# ziggy.net
KiCad netlist of a schematic drawn in EAGLE
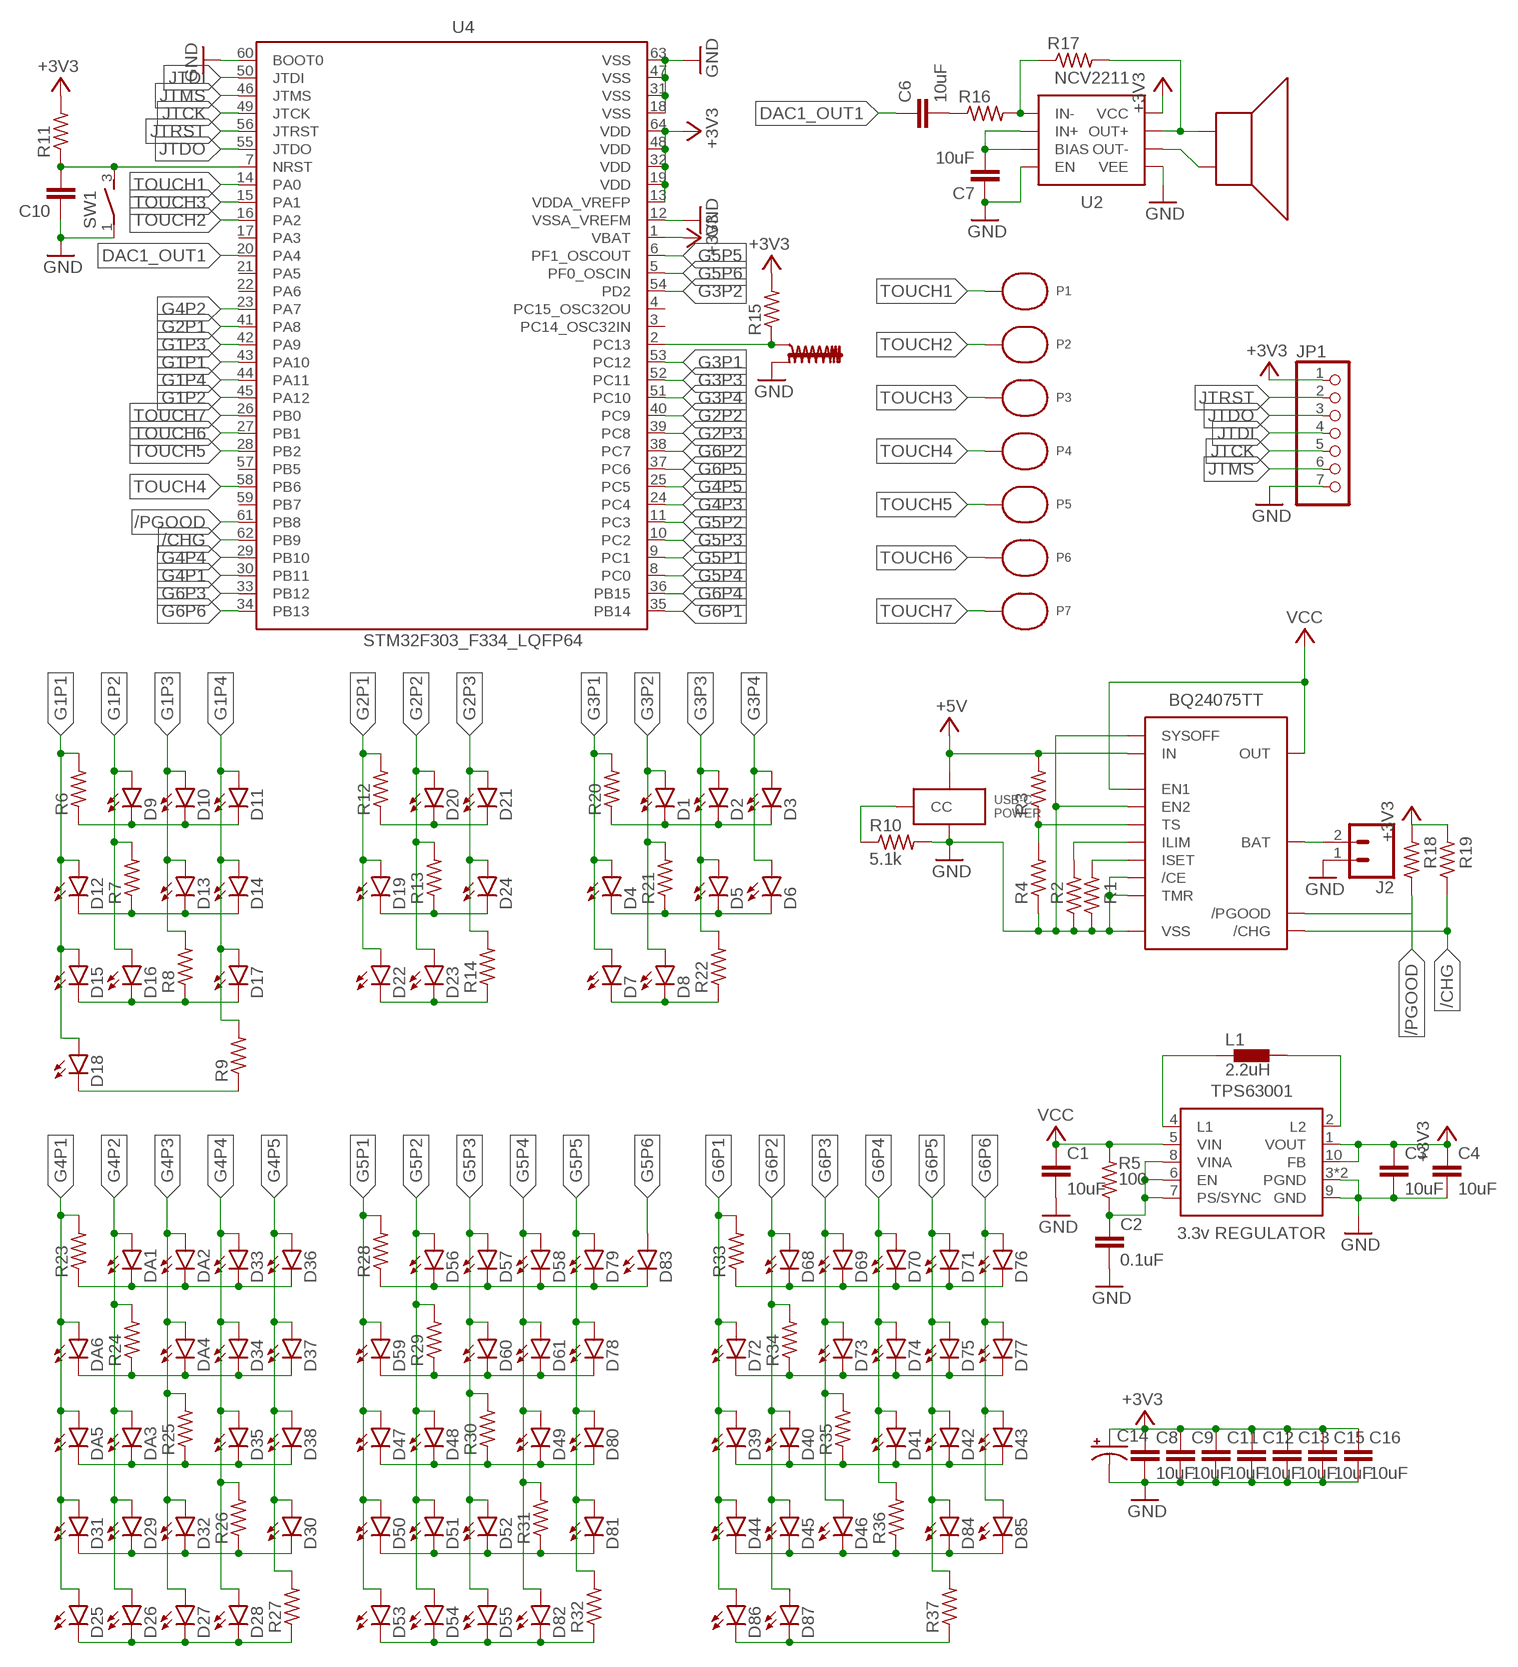
[diagram p0: schematic, sheet 1]

(export (version "E")
  (design (tool "Eeschema 10.0.6"))
  (components
    (comp (ref "C1")
      (value "10uF")
      (footprint "eagle-import:C0805")
      (libsource (lib "eagle-import") (part "C-EUC0805"))
    )
    (comp (ref "C2")
      (value "0.1uF")
      (footprint "eagle-import:C0805")
      (libsource (lib "eagle-import") (part "C-EUC0805"))
    )
    (comp (ref "C3")
      (value "10uF")
      (footprint "eagle-import:C0805")
      (libsource (lib "eagle-import") (part "C-EUC0805"))
    )
    (comp (ref "C4")
      (value "10uF")
      (footprint "eagle-import:C0805")
      (libsource (lib "eagle-import") (part "C-EUC0805"))
    )
    (comp (ref "C6")
      (value "10uF")
      (footprint "eagle-import:C0805")
      (libsource (lib "eagle-import") (part "C-EUC0805"))
    )
    (comp (ref "C7")
      (value "10uF")
      (footprint "eagle-import:C0805")
      (libsource (lib "eagle-import") (part "C-EUC0805"))
    )
    (comp (ref "C8")
      (value "10uF")
      (footprint "eagle-import:C0805")
      (libsource (lib "eagle-import") (part "C-EUC0805"))
    )
    (comp (ref "C9")
      (value "10uF")
      (footprint "eagle-import:C0805")
      (libsource (lib "eagle-import") (part "C-EUC0805"))
    )
    (comp (ref "C10")
      (value "C-EUC0805")
      (footprint "eagle-import:C0805")
      (libsource (lib "eagle-import") (part "C-EUC0805"))
    )
    (comp (ref "C11")
      (value "10uF")
      (footprint "eagle-import:C0805")
      (libsource (lib "eagle-import") (part "C-EUC0805"))
    )
    (comp (ref "C12")
      (value "10uF")
      (footprint "eagle-import:C0805")
      (libsource (lib "eagle-import") (part "C-EUC0805"))
    )
    (comp (ref "C13")
      (value "10uF")
      (footprint "eagle-import:C0805")
      (libsource (lib "eagle-import") (part "C-EUC0805"))
    )
    (comp (ref "C14")
      (value "CPOL-US153CLV-0810")
      (footprint "eagle-import:153CLV-0810")
      (libsource (lib "eagle-import") (part "CPOL-US153CLV-0810"))
    )
    (comp (ref "C15")
      (value "10uF")
      (footprint "eagle-import:C0805")
      (libsource (lib "eagle-import") (part "C-EUC0805"))
    )
    (comp (ref "C16")
      (value "10uF")
      (footprint "eagle-import:C0805")
      (libsource (lib "eagle-import") (part "C-EUC0805"))
    )
    (comp (ref "D1")
      (value "LED-0805")
      (footprint "eagle-import:CHIPLED_0805")
      (libsource (lib "eagle-import") (part "LED-0805"))
    )
    (comp (ref "D2")
      (value "LED-0805")
      (footprint "eagle-import:CHIPLED_0805")
      (libsource (lib "eagle-import") (part "LED-0805"))
    )
    (comp (ref "D3")
      (value "LED-0805")
      (footprint "eagle-import:CHIPLED_0805")
      (libsource (lib "eagle-import") (part "LED-0805"))
    )
    (comp (ref "D4")
      (value "LED-0805")
      (footprint "eagle-import:CHIPLED_0805")
      (libsource (lib "eagle-import") (part "LED-0805"))
    )
    (comp (ref "D5")
      (value "LED-0805")
      (footprint "eagle-import:CHIPLED_0805")
      (libsource (lib "eagle-import") (part "LED-0805"))
    )
    (comp (ref "D6")
      (value "LED-0805")
      (footprint "eagle-import:CHIPLED_0805")
      (libsource (lib "eagle-import") (part "LED-0805"))
    )
    (comp (ref "D7")
      (value "LED-0805")
      (footprint "eagle-import:CHIPLED_0805")
      (libsource (lib "eagle-import") (part "LED-0805"))
    )
    (comp (ref "D8")
      (value "LED-0805")
      (footprint "eagle-import:CHIPLED_0805")
      (libsource (lib "eagle-import") (part "LED-0805"))
    )
    (comp (ref "D9")
      (value "LED-0805")
      (footprint "eagle-import:CHIPLED_0805")
      (libsource (lib "eagle-import") (part "LED-0805"))
    )
    (comp (ref "D10")
      (value "LED-0805")
      (footprint "eagle-import:CHIPLED_0805")
      (libsource (lib "eagle-import") (part "LED-0805"))
    )
    (comp (ref "D11")
      (value "LED-0805")
      (footprint "eagle-import:CHIPLED_0805")
      (libsource (lib "eagle-import") (part "LED-0805"))
    )
    (comp (ref "D12")
      (value "LED-0805")
      (footprint "eagle-import:CHIPLED_0805")
      (libsource (lib "eagle-import") (part "LED-0805"))
    )
    (comp (ref "D13")
      (value "LED-0805")
      (footprint "eagle-import:CHIPLED_0805")
      (libsource (lib "eagle-import") (part "LED-0805"))
    )
    (comp (ref "D14")
      (value "LED-0805")
      (footprint "eagle-import:CHIPLED_0805")
      (libsource (lib "eagle-import") (part "LED-0805"))
    )
    (comp (ref "D15")
      (value "LED-0805")
      (footprint "eagle-import:CHIPLED_0805")
      (libsource (lib "eagle-import") (part "LED-0805"))
    )
    (comp (ref "D16")
      (value "LED-0805")
      (footprint "eagle-import:CHIPLED_0805")
      (libsource (lib "eagle-import") (part "LED-0805"))
    )
    (comp (ref "D17")
      (value "LED-0805")
      (footprint "eagle-import:CHIPLED_0805")
      (libsource (lib "eagle-import") (part "LED-0805"))
    )
    (comp (ref "D18")
      (value "LED-0805")
      (footprint "eagle-import:CHIPLED_0805")
      (libsource (lib "eagle-import") (part "LED-0805"))
    )
    (comp (ref "D19")
      (value "LED-0805")
      (footprint "eagle-import:CHIPLED_0805")
      (libsource (lib "eagle-import") (part "LED-0805"))
    )
    (comp (ref "D20")
      (value "LED-0805")
      (footprint "eagle-import:CHIPLED_0805")
      (libsource (lib "eagle-import") (part "LED-0805"))
    )
    (comp (ref "D21")
      (value "LED-0805")
      (footprint "eagle-import:CHIPLED_0805")
      (libsource (lib "eagle-import") (part "LED-0805"))
    )
    (comp (ref "D22")
      (value "LED-0805")
      (footprint "eagle-import:CHIPLED_0805")
      (libsource (lib "eagle-import") (part "LED-0805"))
    )
    (comp (ref "D23")
      (value "LED-0805")
      (footprint "eagle-import:CHIPLED_0805")
      (libsource (lib "eagle-import") (part "LED-0805"))
    )
    (comp (ref "D24")
      (value "LED-0805")
      (footprint "eagle-import:CHIPLED_0805")
      (libsource (lib "eagle-import") (part "LED-0805"))
    )
    (comp (ref "D25")
      (value "LED-0805")
      (footprint "eagle-import:CHIPLED_0805")
      (libsource (lib "eagle-import") (part "LED-0805"))
    )
    (comp (ref "D26")
      (value "LED-0805")
      (footprint "eagle-import:CHIPLED_0805")
      (libsource (lib "eagle-import") (part "LED-0805"))
    )
    (comp (ref "D27")
      (value "LED-0805")
      (footprint "eagle-import:CHIPLED_0805")
      (libsource (lib "eagle-import") (part "LED-0805"))
    )
    (comp (ref "D28")
      (value "LED-0805")
      (footprint "eagle-import:CHIPLED_0805")
      (libsource (lib "eagle-import") (part "LED-0805"))
    )
    (comp (ref "D29")
      (value "LED-0805")
      (footprint "eagle-import:CHIPLED_0805")
      (libsource (lib "eagle-import") (part "LED-0805"))
    )
    (comp (ref "D30")
      (value "LED-0805")
      (footprint "eagle-import:CHIPLED_0805")
      (libsource (lib "eagle-import") (part "LED-0805"))
    )
    (comp (ref "D31")
      (value "LED-0805")
      (footprint "eagle-import:CHIPLED_0805")
      (libsource (lib "eagle-import") (part "LED-0805"))
    )
    (comp (ref "D32")
      (value "LED-0805")
      (footprint "eagle-import:CHIPLED_0805")
      (libsource (lib "eagle-import") (part "LED-0805"))
    )
    (comp (ref "D33")
      (value "LED-0805")
      (footprint "eagle-import:CHIPLED_0805")
      (libsource (lib "eagle-import") (part "LED-0805"))
    )
    (comp (ref "D34")
      (value "LED-0805")
      (footprint "eagle-import:CHIPLED_0805")
      (libsource (lib "eagle-import") (part "LED-0805"))
    )
    (comp (ref "D35")
      (value "LED-0805")
      (footprint "eagle-import:CHIPLED_0805")
      (libsource (lib "eagle-import") (part "LED-0805"))
    )
    (comp (ref "D36")
      (value "LED-0805")
      (footprint "eagle-import:CHIPLED_0805")
      (libsource (lib "eagle-import") (part "LED-0805"))
    )
    (comp (ref "D37")
      (value "LED-0805")
      (footprint "eagle-import:CHIPLED_0805")
      (libsource (lib "eagle-import") (part "LED-0805"))
    )
    (comp (ref "D38")
      (value "LED-0805")
      (footprint "eagle-import:CHIPLED_0805")
      (libsource (lib "eagle-import") (part "LED-0805"))
    )
    (comp (ref "D39")
      (value "LED-0805")
      (footprint "eagle-import:CHIPLED_0805")
      (libsource (lib "eagle-import") (part "LED-0805"))
    )
    (comp (ref "D40")
      (value "LED-0805")
      (footprint "eagle-import:CHIPLED_0805")
      (libsource (lib "eagle-import") (part "LED-0805"))
    )
    (comp (ref "D41")
      (value "LED-0805")
      (footprint "eagle-import:CHIPLED_0805")
      (libsource (lib "eagle-import") (part "LED-0805"))
    )
    (comp (ref "D42")
      (value "LED-0805")
      (footprint "eagle-import:CHIPLED_0805")
      (libsource (lib "eagle-import") (part "LED-0805"))
    )
    (comp (ref "D43")
      (value "LED-0805")
      (footprint "eagle-import:CHIPLED_0805")
      (libsource (lib "eagle-import") (part "LED-0805"))
    )
    (comp (ref "D44")
      (value "LED-0805")
      (footprint "eagle-import:CHIPLED_0805")
      (libsource (lib "eagle-import") (part "LED-0805"))
    )
    (comp (ref "D45")
      (value "LED-0805")
      (footprint "eagle-import:CHIPLED_0805")
      (libsource (lib "eagle-import") (part "LED-0805"))
    )
    (comp (ref "D46")
      (value "LED-0805")
      (footprint "eagle-import:CHIPLED_0805")
      (libsource (lib "eagle-import") (part "LED-0805"))
    )
    (comp (ref "D47")
      (value "LED-0805")
      (footprint "eagle-import:CHIPLED_0805")
      (libsource (lib "eagle-import") (part "LED-0805"))
    )
    (comp (ref "D48")
      (value "LED-0805")
      (footprint "eagle-import:CHIPLED_0805")
      (libsource (lib "eagle-import") (part "LED-0805"))
    )
    (comp (ref "D49")
      (value "LED-0805")
      (footprint "eagle-import:CHIPLED_0805")
      (libsource (lib "eagle-import") (part "LED-0805"))
    )
    (comp (ref "D50")
      (value "LED-0805")
      (footprint "eagle-import:CHIPLED_0805")
      (libsource (lib "eagle-import") (part "LED-0805"))
    )
    (comp (ref "D51")
      (value "LED-0805")
      (footprint "eagle-import:CHIPLED_0805")
      (libsource (lib "eagle-import") (part "LED-0805"))
    )
    (comp (ref "D52")
      (value "LED-0805")
      (footprint "eagle-import:CHIPLED_0805")
      (libsource (lib "eagle-import") (part "LED-0805"))
    )
    (comp (ref "D53")
      (value "LED-0805")
      (footprint "eagle-import:CHIPLED_0805")
      (libsource (lib "eagle-import") (part "LED-0805"))
    )
    (comp (ref "D54")
      (value "LED-0805")
      (footprint "eagle-import:CHIPLED_0805")
      (libsource (lib "eagle-import") (part "LED-0805"))
    )
    (comp (ref "D55")
      (value "LED-0805")
      (footprint "eagle-import:CHIPLED_0805")
      (libsource (lib "eagle-import") (part "LED-0805"))
    )
    (comp (ref "D56")
      (value "LED-0805")
      (footprint "eagle-import:CHIPLED_0805")
      (libsource (lib "eagle-import") (part "LED-0805"))
    )
    (comp (ref "D57")
      (value "LED-0805")
      (footprint "eagle-import:CHIPLED_0805")
      (libsource (lib "eagle-import") (part "LED-0805"))
    )
    (comp (ref "D58")
      (value "LED-0805")
      (footprint "eagle-import:CHIPLED_0805")
      (libsource (lib "eagle-import") (part "LED-0805"))
    )
    (comp (ref "D59")
      (value "LED-0805")
      (footprint "eagle-import:CHIPLED_0805")
      (libsource (lib "eagle-import") (part "LED-0805"))
    )
    (comp (ref "D60")
      (value "LED-0805")
      (footprint "eagle-import:CHIPLED_0805")
      (libsource (lib "eagle-import") (part "LED-0805"))
    )
    (comp (ref "D61")
      (value "LED-0805")
      (footprint "eagle-import:CHIPLED_0805")
      (libsource (lib "eagle-import") (part "LED-0805"))
    )
    (comp (ref "D68")
      (value "LED-0805")
      (footprint "eagle-import:CHIPLED_0805")
      (libsource (lib "eagle-import") (part "LED-0805"))
    )
    (comp (ref "D69")
      (value "LED-0805")
      (footprint "eagle-import:CHIPLED_0805")
      (libsource (lib "eagle-import") (part "LED-0805"))
    )
    (comp (ref "D70")
      (value "LED-0805")
      (footprint "eagle-import:CHIPLED_0805")
      (libsource (lib "eagle-import") (part "LED-0805"))
    )
    (comp (ref "D71")
      (value "LED-0805")
      (footprint "eagle-import:CHIPLED_0805")
      (libsource (lib "eagle-import") (part "LED-0805"))
    )
    (comp (ref "D72")
      (value "LED-0805")
      (footprint "eagle-import:CHIPLED_0805")
      (libsource (lib "eagle-import") (part "LED-0805"))
    )
    (comp (ref "D73")
      (value "LED-0805")
      (footprint "eagle-import:CHIPLED_0805")
      (libsource (lib "eagle-import") (part "LED-0805"))
    )
    (comp (ref "D74")
      (value "LED-0805")
      (footprint "eagle-import:CHIPLED_0805")
      (libsource (lib "eagle-import") (part "LED-0805"))
    )
    (comp (ref "D75")
      (value "LED-0805")
      (footprint "eagle-import:CHIPLED_0805")
      (libsource (lib "eagle-import") (part "LED-0805"))
    )
    (comp (ref "D76")
      (value "LED-0805")
      (footprint "eagle-import:CHIPLED_0805")
      (libsource (lib "eagle-import") (part "LED-0805"))
    )
    (comp (ref "D77")
      (value "LED-0805")
      (footprint "eagle-import:CHIPLED_0805")
      (libsource (lib "eagle-import") (part "LED-0805"))
    )
    (comp (ref "D78")
      (value "LED-0805")
      (footprint "eagle-import:CHIPLED_0805")
      (libsource (lib "eagle-import") (part "LED-0805"))
    )
    (comp (ref "D79")
      (value "LED-0805")
      (footprint "eagle-import:CHIPLED_0805")
      (libsource (lib "eagle-import") (part "LED-0805"))
    )
    (comp (ref "D80")
      (value "LED-0805")
      (footprint "eagle-import:CHIPLED_0805")
      (libsource (lib "eagle-import") (part "LED-0805"))
    )
    (comp (ref "D81")
      (value "LED-0805")
      (footprint "eagle-import:CHIPLED_0805")
      (libsource (lib "eagle-import") (part "LED-0805"))
    )
    (comp (ref "D82")
      (value "LED-0805")
      (footprint "eagle-import:CHIPLED_0805")
      (libsource (lib "eagle-import") (part "LED-0805"))
    )
    (comp (ref "D83")
      (value "LED-0805")
      (footprint "eagle-import:CHIPLED_0805")
      (libsource (lib "eagle-import") (part "LED-0805"))
    )
    (comp (ref "D84")
      (value "LED-0805")
      (footprint "eagle-import:CHIPLED_0805")
      (libsource (lib "eagle-import") (part "LED-0805"))
    )
    (comp (ref "D85")
      (value "LED-0805")
      (footprint "eagle-import:CHIPLED_0805")
      (libsource (lib "eagle-import") (part "LED-0805"))
    )
    (comp (ref "D86")
      (value "LED-0805")
      (footprint "eagle-import:CHIPLED_0805")
      (libsource (lib "eagle-import") (part "LED-0805"))
    )
    (comp (ref "D87")
      (value "LED-0805")
      (footprint "eagle-import:CHIPLED_0805")
      (libsource (lib "eagle-import") (part "LED-0805"))
    )
    (comp (ref "DA1")
      (value "LED-0805")
      (footprint "eagle-import:CHIPLED_0805")
      (libsource (lib "eagle-import") (part "LED-0805"))
    )
    (comp (ref "DA2")
      (value "LED-0805")
      (footprint "eagle-import:CHIPLED_0805")
      (libsource (lib "eagle-import") (part "LED-0805"))
    )
    (comp (ref "DA3")
      (value "LED-0805")
      (footprint "eagle-import:CHIPLED_0805")
      (libsource (lib "eagle-import") (part "LED-0805"))
    )
    (comp (ref "DA4")
      (value "LED-0805")
      (footprint "eagle-import:CHIPLED_0805")
      (libsource (lib "eagle-import") (part "LED-0805"))
    )
    (comp (ref "DA5")
      (value "LED-0805")
      (footprint "eagle-import:CHIPLED_0805")
      (libsource (lib "eagle-import") (part "LED-0805"))
    )
    (comp (ref "DA6")
      (value "LED-0805")
      (footprint "eagle-import:CHIPLED_0805")
      (libsource (lib "eagle-import") (part "LED-0805"))
    )
    (comp (ref "J1")
      (value "USB-C-POWER")
      (footprint "eagle-import:USB-C")
      (libsource (lib "eagle-import") (part "USB-C-POWER"))
    )
    (comp (ref "J2")
      (value "CONN_02-JST-2MM-SMT")
      (footprint "eagle-import:JST-2-SMD")
      (libsource (lib "eagle-import") (part "CONN_02-JST-2MM-SMT"))
    )
    (comp (ref "JP1")
      (value "PINHD-1X7/90")
      (footprint "eagle-import:1X07_90")
      (libsource (lib "eagle-import") (part "PINHD-1X7/90"))
    )
    (comp (ref "L1")
      (value "2.2uH")
      (footprint "eagle-import:LPS3015")
      (libsource (lib "eagle-import") (part "LPS3015"))
    )
    (comp (ref "P1")
      (value "CAPTOUCH")
      (footprint "eagle-import:CAPTOUCH")
      (libsource (lib "eagle-import") (part "CAPTOUCH"))
    )
    (comp (ref "P2")
      (value "CAPTOUCH")
      (footprint "eagle-import:CAPTOUCH")
      (libsource (lib "eagle-import") (part "CAPTOUCH"))
    )
    (comp (ref "P3")
      (value "CAPTOUCH")
      (footprint "eagle-import:CAPTOUCH")
      (libsource (lib "eagle-import") (part "CAPTOUCH"))
    )
    (comp (ref "P4")
      (value "CAPTOUCH")
      (footprint "eagle-import:CAPTOUCH")
      (libsource (lib "eagle-import") (part "CAPTOUCH"))
    )
    (comp (ref "P5")
      (value "CAPTOUCH")
      (footprint "eagle-import:CAPTOUCH")
      (libsource (lib "eagle-import") (part "CAPTOUCH"))
    )
    (comp (ref "P6")
      (value "CAPTOUCH")
      (footprint "eagle-import:CAPTOUCH")
      (libsource (lib "eagle-import") (part "CAPTOUCH"))
    )
    (comp (ref "P7")
      (value "CAPTOUCH")
      (footprint "eagle-import:CAPTOUCH")
      (libsource (lib "eagle-import") (part "CAPTOUCH"))
    )
    (comp (ref "R1")
      (value "R-US_R0805")
      (footprint "eagle-import:R0805")
      (libsource (lib "eagle-import") (part "R-US_R0805"))
    )
    (comp (ref "R2")
      (value "R-US_R0805")
      (footprint "eagle-import:R0805")
      (libsource (lib "eagle-import") (part "R-US_R0805"))
    )
    (comp (ref "R3")
      (value "R-US_R0805")
      (footprint "eagle-import:R0805")
      (libsource (lib "eagle-import") (part "R-US_R0805"))
    )
    (comp (ref "R4")
      (value "R-US_R0805")
      (footprint "eagle-import:R0805")
      (libsource (lib "eagle-import") (part "R-US_R0805"))
    )
    (comp (ref "R5")
      (value "100")
      (footprint "eagle-import:R0805")
      (libsource (lib "eagle-import") (part "R-US_R0805"))
    )
    (comp (ref "R6")
      (value "R-US_R0805")
      (footprint "eagle-import:R0805")
      (libsource (lib "eagle-import") (part "R-US_R0805"))
    )
    (comp (ref "R7")
      (value "R-US_R0805")
      (footprint "eagle-import:R0805")
      (libsource (lib "eagle-import") (part "R-US_R0805"))
    )
    (comp (ref "R8")
      (value "R-US_R0805")
      (footprint "eagle-import:R0805")
      (libsource (lib "eagle-import") (part "R-US_R0805"))
    )
    (comp (ref "R9")
      (value "R-US_R0805")
      (footprint "eagle-import:R0805")
      (libsource (lib "eagle-import") (part "R-US_R0805"))
    )
    (comp (ref "R10")
      (value "5.1k")
      (footprint "eagle-import:R0805")
      (libsource (lib "eagle-import") (part "R-US_R0805"))
    )
    (comp (ref "R11")
      (value "R-US_R0805")
      (footprint "eagle-import:R0805")
      (libsource (lib "eagle-import") (part "R-US_R0805"))
    )
    (comp (ref "R12")
      (value "R-US_R0805")
      (footprint "eagle-import:R0805")
      (libsource (lib "eagle-import") (part "R-US_R0805"))
    )
    (comp (ref "R13")
      (value "R-US_R0805")
      (footprint "eagle-import:R0805")
      (libsource (lib "eagle-import") (part "R-US_R0805"))
    )
    (comp (ref "R14")
      (value "R-US_R0805")
      (footprint "eagle-import:R0805")
      (libsource (lib "eagle-import") (part "R-US_R0805"))
    )
    (comp (ref "R15")
      (value "R-US_R0805")
      (footprint "eagle-import:R0805")
      (libsource (lib "eagle-import") (part "R-US_R0805"))
    )
    (comp (ref "R16")
      (value "R-US_R0805")
      (footprint "eagle-import:R0805")
      (libsource (lib "eagle-import") (part "R-US_R0805"))
    )
    (comp (ref "R17")
      (value "R-US_R0805")
      (footprint "eagle-import:R0805")
      (libsource (lib "eagle-import") (part "R-US_R0805"))
    )
    (comp (ref "R18")
      (value "R-US_R0805")
      (footprint "eagle-import:R0805")
      (libsource (lib "eagle-import") (part "R-US_R0805"))
    )
    (comp (ref "R19")
      (value "R-US_R0805")
      (footprint "eagle-import:R0805")
      (libsource (lib "eagle-import") (part "R-US_R0805"))
    )
    (comp (ref "R20")
      (value "R-US_R0805")
      (footprint "eagle-import:R0805")
      (libsource (lib "eagle-import") (part "R-US_R0805"))
    )
    (comp (ref "R21")
      (value "R-US_R0805")
      (footprint "eagle-import:R0805")
      (libsource (lib "eagle-import") (part "R-US_R0805"))
    )
    (comp (ref "R22")
      (value "R-US_R0805")
      (footprint "eagle-import:R0805")
      (libsource (lib "eagle-import") (part "R-US_R0805"))
    )
    (comp (ref "R23")
      (value "R-US_R0805")
      (footprint "eagle-import:R0805")
      (libsource (lib "eagle-import") (part "R-US_R0805"))
    )
    (comp (ref "R24")
      (value "R-US_R0805")
      (footprint "eagle-import:R0805")
      (libsource (lib "eagle-import") (part "R-US_R0805"))
    )
    (comp (ref "R25")
      (value "R-US_R0805")
      (footprint "eagle-import:R0805")
      (libsource (lib "eagle-import") (part "R-US_R0805"))
    )
    (comp (ref "R26")
      (value "R-US_R0805")
      (footprint "eagle-import:R0805")
      (libsource (lib "eagle-import") (part "R-US_R0805"))
    )
    (comp (ref "R27")
      (value "R-US_R0805")
      (footprint "eagle-import:R0805")
      (libsource (lib "eagle-import") (part "R-US_R0805"))
    )
    (comp (ref "R28")
      (value "R-US_R0805")
      (footprint "eagle-import:R0805")
      (libsource (lib "eagle-import") (part "R-US_R0805"))
    )
    (comp (ref "R29")
      (value "R-US_R0805")
      (footprint "eagle-import:R0805")
      (libsource (lib "eagle-import") (part "R-US_R0805"))
    )
    (comp (ref "R30")
      (value "R-US_R0805")
      (footprint "eagle-import:R0805")
      (libsource (lib "eagle-import") (part "R-US_R0805"))
    )
    (comp (ref "R31")
      (value "R-US_R0805")
      (footprint "eagle-import:R0805")
      (libsource (lib "eagle-import") (part "R-US_R0805"))
    )
    (comp (ref "R32")
      (value "R-US_R0805")
      (footprint "eagle-import:R0805")
      (libsource (lib "eagle-import") (part "R-US_R0805"))
    )
    (comp (ref "R33")
      (value "R-US_R0805")
      (footprint "eagle-import:R0805")
      (libsource (lib "eagle-import") (part "R-US_R0805"))
    )
    (comp (ref "R34")
      (value "R-US_R0805")
      (footprint "eagle-import:R0805")
      (libsource (lib "eagle-import") (part "R-US_R0805"))
    )
    (comp (ref "R35")
      (value "R-US_R0805")
      (footprint "eagle-import:R0805")
      (libsource (lib "eagle-import") (part "R-US_R0805"))
    )
    (comp (ref "R36")
      (value "R-US_R0805")
      (footprint "eagle-import:R0805")
      (libsource (lib "eagle-import") (part "R-US_R0805"))
    )
    (comp (ref "R37")
      (value "R-US_R0805")
      (footprint "eagle-import:R0805")
      (libsource (lib "eagle-import") (part "R-US_R0805"))
    )
    (comp (ref "SP1")
      (value "CMS-151103-088SP")
      (footprint "eagle-import:CMS-151103")
      (libsource (lib "eagle-import") (part "CMS-151103-088SP"))
    )
    (comp (ref "SW1")
      (value "AS11CH")
      (footprint "eagle-import:AS11CH")
      (libsource (lib "eagle-import") (part "AS11CH"))
    )
    (comp (ref "SW2")
      (value "ADAFRUIT1767")
      (footprint "eagle-import:ADAFRUIT1767")
      (libsource (lib "eagle-import") (part "ADAFRUIT1767"))
    )
    (comp (ref "U1")
      (value "BQ24075TT")
      (footprint "eagle-import:QFN50P300X300X100-17T168N")
      (libsource (lib "eagle-import") (part "BQ24075TT"))
    )
    (comp (ref "U2")
      (value "NCV2211")
      (footprint "eagle-import:SOIC127P600X175-8N")
      (libsource (lib "eagle-import") (part "NCV2211"))
    )
    (comp (ref "U3")
      (value "TPS63001")
      (footprint "eagle-import:SON50P300X300X100-11T165X240N")
      (libsource (lib "eagle-import") (part "TPS63001"))
    )
    (comp (ref "U4")
      (value "STM32F303_F334_LQFP64")
      (footprint "eagle-import:LQFP64_PACKAGE")
      (libsource (lib "eagle-import") (part "STM32F303_F334_LQFP64"))
    )
  )
  (nets
    (net (code "1") (name "+3V3") (class "Default")
      (node (ref "C11") (pin "1") (pinfunction "1_1") (pintype "passive"))
      (node (ref "C12") (pin "1") (pinfunction "1_1") (pintype "passive"))
      (node (ref "C13") (pin "1") (pinfunction "1_1") (pintype "passive"))
      (node (ref "C14") (pin "+") (pinfunction "+_+") (pintype "passive"))
      (node (ref "C15") (pin "1") (pinfunction "1_1") (pintype "passive"))
      (node (ref "C16") (pin "1") (pinfunction "1_1") (pintype "passive"))
      (node (ref "C3") (pin "1") (pinfunction "1_1") (pintype "passive"))
      (node (ref "C4") (pin "1") (pinfunction "1_1") (pintype "passive"))
      (node (ref "C8") (pin "1") (pinfunction "1_1") (pintype "passive"))
      (node (ref "C9") (pin "1") (pinfunction "1_1") (pintype "passive"))
      (node (ref "JP1") (pin "1") (pinfunction "1_1") (pintype "passive"))
      (node (ref "R11") (pin "2") (pinfunction "2_2") (pintype "passive"))
      (node (ref "R15") (pin "2") (pinfunction "2_2") (pintype "passive"))
      (node (ref "R18") (pin "2") (pinfunction "2_2") (pintype "passive"))
      (node (ref "R19") (pin "2") (pinfunction "2_2") (pintype "passive"))
      (node (ref "U2") (pin "6") (pinfunction "VCC_6") (pintype "power_in"))
      (node (ref "U3") (pin "1") (pinfunction "VOUT_1") (pintype "passive"))
      (node (ref "U3") (pin "10") (pinfunction "FB_10") (pintype "passive"))
      (node (ref "U4") (pin "1") (pinfunction "VBAT_1") (pintype "passive"))
      (node (ref "U4") (pin "13") (pinfunction "VDDA_VREFP_13") (pintype "power_in"))
      (node (ref "U4") (pin "19") (pinfunction "VDD_19") (pintype "power_in"))
      (node (ref "U4") (pin "32") (pinfunction "VDD_32") (pintype "power_in"))
      (node (ref "U4") (pin "48") (pinfunction "VDD_48") (pintype "power_in"))
      (node (ref "U4") (pin "64") (pinfunction "VDD_64") (pintype "power_in"))
    )
    (net (code "2") (name "+5V") (class "Default")
      (node (ref "J1") (pin "VBUS1") (pinfunction "VBUS_VBUS1") (pintype "bidirectional"))
      (node (ref "J1") (pin "VBUS2") (pinfunction "VBUS_VBUS2") (pintype "bidirectional"))
      (node (ref "R3") (pin "2") (pinfunction "2_2") (pintype "passive"))
      (node (ref "U1") (pin "13") (pinfunction "IN_13") (pintype "bidirectional"))
    )
    (net (code "3") (name "DAC1_OUT1") (class "Default")
      (node (ref "C6") (pin "1") (pinfunction "1_1") (pintype "passive"))
      (node (ref "U4") (pin "20") (pinfunction "PA4_20") (pintype "bidirectional"))
    )
    (net (code "4") (name "G1P1") (class "Default")
      (node (ref "D12") (pin "A") (pinfunction "A_A") (pintype "passive"))
      (node (ref "D15") (pin "A") (pinfunction "A_A") (pintype "passive"))
      (node (ref "D18") (pin "A") (pinfunction "A_A") (pintype "passive"))
      (node (ref "R6") (pin "2") (pinfunction "2_2") (pintype "passive"))
      (node (ref "U4") (pin "43") (pinfunction "PA10_43") (pintype "bidirectional"))
    )
    (net (code "5") (name "G1P2") (class "Default")
      (node (ref "D16") (pin "A") (pinfunction "A_A") (pintype "passive"))
      (node (ref "D9") (pin "A") (pinfunction "A_A") (pintype "passive"))
      (node (ref "R7") (pin "2") (pinfunction "2_2") (pintype "passive"))
      (node (ref "U4") (pin "45") (pinfunction "PA12_45") (pintype "bidirectional"))
    )
    (net (code "6") (name "G1P3") (class "Default")
      (node (ref "D10") (pin "A") (pinfunction "A_A") (pintype "passive"))
      (node (ref "D13") (pin "A") (pinfunction "A_A") (pintype "passive"))
      (node (ref "R8") (pin "2") (pinfunction "2_2") (pintype "passive"))
      (node (ref "U4") (pin "42") (pinfunction "PA9_42") (pintype "bidirectional"))
    )
    (net (code "7") (name "G1P4") (class "Default")
      (node (ref "D11") (pin "A") (pinfunction "A_A") (pintype "passive"))
      (node (ref "D14") (pin "A") (pinfunction "A_A") (pintype "passive"))
      (node (ref "D17") (pin "A") (pinfunction "A_A") (pintype "passive"))
      (node (ref "R9") (pin "2") (pinfunction "2_2") (pintype "passive"))
      (node (ref "U4") (pin "44") (pinfunction "PA11_44") (pintype "bidirectional"))
    )
    (net (code "8") (name "G2P1") (class "Default")
      (node (ref "D19") (pin "A") (pinfunction "A_A") (pintype "passive"))
      (node (ref "D22") (pin "A") (pinfunction "A_A") (pintype "passive"))
      (node (ref "R12") (pin "2") (pinfunction "2_2") (pintype "passive"))
      (node (ref "U4") (pin "41") (pinfunction "PA8_41") (pintype "bidirectional"))
    )
    (net (code "9") (name "G2P2") (class "Default")
      (node (ref "D20") (pin "A") (pinfunction "A_A") (pintype "passive"))
      (node (ref "D23") (pin "A") (pinfunction "A_A") (pintype "passive"))
      (node (ref "R13") (pin "2") (pinfunction "2_2") (pintype "passive"))
      (node (ref "U4") (pin "40") (pinfunction "PC9_40") (pintype "bidirectional"))
    )
    (net (code "10") (name "G2P3") (class "Default")
      (node (ref "D21") (pin "A") (pinfunction "A_A") (pintype "passive"))
      (node (ref "D24") (pin "A") (pinfunction "A_A") (pintype "passive"))
      (node (ref "R14") (pin "2") (pinfunction "2_2") (pintype "passive"))
      (node (ref "U4") (pin "39") (pinfunction "PC8_39") (pintype "bidirectional"))
    )
    (net (code "11") (name "G3P1") (class "Default")
      (node (ref "D4") (pin "A") (pinfunction "A_A") (pintype "passive"))
      (node (ref "D7") (pin "A") (pinfunction "A_A") (pintype "passive"))
      (node (ref "R20") (pin "2") (pinfunction "2_2") (pintype "passive"))
      (node (ref "U4") (pin "53") (pinfunction "PC12_53") (pintype "bidirectional"))
    )
    (net (code "12") (name "G3P2") (class "Default")
      (node (ref "D1") (pin "A") (pinfunction "A_A") (pintype "passive"))
      (node (ref "D8") (pin "A") (pinfunction "A_A") (pintype "passive"))
      (node (ref "R21") (pin "2") (pinfunction "2_2") (pintype "passive"))
      (node (ref "U4") (pin "54") (pinfunction "PD2_54") (pintype "bidirectional"))
    )
    (net (code "13") (name "G3P3") (class "Default")
      (node (ref "D2") (pin "A") (pinfunction "A_A") (pintype "passive"))
      (node (ref "D5") (pin "A") (pinfunction "A_A") (pintype "passive"))
      (node (ref "R22") (pin "2") (pinfunction "2_2") (pintype "passive"))
      (node (ref "U4") (pin "52") (pinfunction "PC11_52") (pintype "bidirectional"))
    )
    (net (code "14") (name "G3P4") (class "Default")
      (node (ref "D3") (pin "A") (pinfunction "A_A") (pintype "passive"))
      (node (ref "D6") (pin "A") (pinfunction "A_A") (pintype "passive"))
      (node (ref "U4") (pin "51") (pinfunction "PC10_51") (pintype "bidirectional"))
    )
    (net (code "15") (name "G4P1") (class "Default")
      (node (ref "D25") (pin "A") (pinfunction "A_A") (pintype "passive"))
      (node (ref "D31") (pin "A") (pinfunction "A_A") (pintype "passive"))
      (node (ref "DA5") (pin "A") (pinfunction "A_A") (pintype "passive"))
      (node (ref "DA6") (pin "A") (pinfunction "A_A") (pintype "passive"))
      (node (ref "R23") (pin "2") (pinfunction "2_2") (pintype "passive"))
      (node (ref "U4") (pin "30") (pinfunction "PB11_30") (pintype "bidirectional"))
    )
    (net (code "16") (name "G4P2") (class "Default")
      (node (ref "D26") (pin "A") (pinfunction "A_A") (pintype "passive"))
      (node (ref "D29") (pin "A") (pinfunction "A_A") (pintype "passive"))
      (node (ref "DA1") (pin "A") (pinfunction "A_A") (pintype "passive"))
      (node (ref "DA3") (pin "A") (pinfunction "A_A") (pintype "passive"))
      (node (ref "R24") (pin "2") (pinfunction "2_2") (pintype "passive"))
      (node (ref "U4") (pin "23") (pinfunction "PA7_23") (pintype "bidirectional"))
    )
    (net (code "17") (name "G4P3") (class "Default")
      (node (ref "D27") (pin "A") (pinfunction "A_A") (pintype "passive"))
      (node (ref "D32") (pin "A") (pinfunction "A_A") (pintype "passive"))
      (node (ref "DA2") (pin "A") (pinfunction "A_A") (pintype "passive"))
      (node (ref "DA4") (pin "A") (pinfunction "A_A") (pintype "passive"))
      (node (ref "R25") (pin "2") (pinfunction "2_2") (pintype "passive"))
      (node (ref "U4") (pin "24") (pinfunction "PC4_24") (pintype "bidirectional"))
    )
    (net (code "18") (name "G4P4") (class "Default")
      (node (ref "D28") (pin "A") (pinfunction "A_A") (pintype "passive"))
      (node (ref "D33") (pin "A") (pinfunction "A_A") (pintype "passive"))
      (node (ref "D34") (pin "A") (pinfunction "A_A") (pintype "passive"))
      (node (ref "D35") (pin "A") (pinfunction "A_A") (pintype "passive"))
      (node (ref "R26") (pin "2") (pinfunction "2_2") (pintype "passive"))
      (node (ref "U4") (pin "29") (pinfunction "PB10_29") (pintype "bidirectional"))
    )
    (net (code "19") (name "G4P5") (class "Default")
      (node (ref "D30") (pin "A") (pinfunction "A_A") (pintype "passive"))
      (node (ref "D36") (pin "A") (pinfunction "A_A") (pintype "passive"))
      (node (ref "D37") (pin "A") (pinfunction "A_A") (pintype "passive"))
      (node (ref "D38") (pin "A") (pinfunction "A_A") (pintype "passive"))
      (node (ref "R27") (pin "2") (pinfunction "2_2") (pintype "passive"))
      (node (ref "U4") (pin "25") (pinfunction "PC5_25") (pintype "bidirectional"))
    )
    (net (code "20") (name "G5P1") (class "Default")
      (node (ref "D47") (pin "A") (pinfunction "A_A") (pintype "passive"))
      (node (ref "D50") (pin "A") (pinfunction "A_A") (pintype "passive"))
      (node (ref "D53") (pin "A") (pinfunction "A_A") (pintype "passive"))
      (node (ref "D59") (pin "A") (pinfunction "A_A") (pintype "passive"))
      (node (ref "R28") (pin "2") (pinfunction "2_2") (pintype "passive"))
      (node (ref "U4") (pin "9") (pinfunction "PC1_9") (pintype "bidirectional"))
    )
    (net (code "21") (name "G5P2") (class "Default")
      (node (ref "D48") (pin "A") (pinfunction "A_A") (pintype "passive"))
      (node (ref "D51") (pin "A") (pinfunction "A_A") (pintype "passive"))
      (node (ref "D54") (pin "A") (pinfunction "A_A") (pintype "passive"))
      (node (ref "D56") (pin "A") (pinfunction "A_A") (pintype "passive"))
      (node (ref "R29") (pin "2") (pinfunction "2_2") (pintype "passive"))
      (node (ref "U4") (pin "11") (pinfunction "PC3_11") (pintype "bidirectional"))
    )
    (net (code "22") (name "G5P3") (class "Default")
      (node (ref "D52") (pin "A") (pinfunction "A_A") (pintype "passive"))
      (node (ref "D55") (pin "A") (pinfunction "A_A") (pintype "passive"))
      (node (ref "D57") (pin "A") (pinfunction "A_A") (pintype "passive"))
      (node (ref "D60") (pin "A") (pinfunction "A_A") (pintype "passive"))
      (node (ref "R30") (pin "2") (pinfunction "2_2") (pintype "passive"))
      (node (ref "U4") (pin "10") (pinfunction "PC2_10") (pintype "bidirectional"))
    )
    (net (code "23") (name "G5P4") (class "Default")
      (node (ref "D49") (pin "A") (pinfunction "A_A") (pintype "passive"))
      (node (ref "D58") (pin "A") (pinfunction "A_A") (pintype "passive"))
      (node (ref "D61") (pin "A") (pinfunction "A_A") (pintype "passive"))
      (node (ref "D82") (pin "A") (pinfunction "A_A") (pintype "passive"))
      (node (ref "R31") (pin "2") (pinfunction "2_2") (pintype "passive"))
      (node (ref "U4") (pin "8") (pinfunction "PC0_8") (pintype "bidirectional"))
    )
    (net (code "24") (name "G5P5") (class "Default")
      (node (ref "D78") (pin "A") (pinfunction "A_A") (pintype "passive"))
      (node (ref "D79") (pin "A") (pinfunction "A_A") (pintype "passive"))
      (node (ref "D80") (pin "A") (pinfunction "A_A") (pintype "passive"))
      (node (ref "D81") (pin "A") (pinfunction "A_A") (pintype "passive"))
      (node (ref "R32") (pin "2") (pinfunction "2_2") (pintype "passive"))
      (node (ref "U4") (pin "6") (pinfunction "PF1_OSCOUT_6") (pintype "bidirectional"))
    )
    (net (code "25") (name "G5P6") (class "Default")
      (node (ref "D83") (pin "A") (pinfunction "A_A") (pintype "passive"))
      (node (ref "U4") (pin "5") (pinfunction "PF0_OSCIN_5") (pintype "bidirectional"))
    )
    (net (code "26") (name "G6P1") (class "Default")
      (node (ref "D39") (pin "A") (pinfunction "A_A") (pintype "passive"))
      (node (ref "D44") (pin "A") (pinfunction "A_A") (pintype "passive"))
      (node (ref "D72") (pin "A") (pinfunction "A_A") (pintype "passive"))
      (node (ref "D86") (pin "A") (pinfunction "A_A") (pintype "passive"))
      (node (ref "R33") (pin "2") (pinfunction "2_2") (pintype "passive"))
      (node (ref "U4") (pin "35") (pinfunction "PB14_35") (pintype "bidirectional"))
    )
    (net (code "27") (name "G6P2") (class "Default")
      (node (ref "D40") (pin "A") (pinfunction "A_A") (pintype "passive"))
      (node (ref "D45") (pin "A") (pinfunction "A_A") (pintype "passive"))
      (node (ref "D68") (pin "A") (pinfunction "A_A") (pintype "passive"))
      (node (ref "D87") (pin "A") (pinfunction "A_A") (pintype "passive"))
      (node (ref "R34") (pin "2") (pinfunction "2_2") (pintype "passive"))
      (node (ref "U4") (pin "38") (pinfunction "PC7_38") (pintype "bidirectional"))
    )
    (net (code "28") (name "G6P3") (class "Default")
      (node (ref "D46") (pin "A") (pinfunction "A_A") (pintype "passive"))
      (node (ref "D69") (pin "A") (pinfunction "A_A") (pintype "passive"))
      (node (ref "D73") (pin "A") (pinfunction "A_A") (pintype "passive"))
      (node (ref "R35") (pin "2") (pinfunction "2_2") (pintype "passive"))
      (node (ref "U4") (pin "33") (pinfunction "PB12_33") (pintype "bidirectional"))
    )
    (net (code "29") (name "G6P4") (class "Default")
      (node (ref "D41") (pin "A") (pinfunction "A_A") (pintype "passive"))
      (node (ref "D70") (pin "A") (pinfunction "A_A") (pintype "passive"))
      (node (ref "D74") (pin "A") (pinfunction "A_A") (pintype "passive"))
      (node (ref "R36") (pin "2") (pinfunction "2_2") (pintype "passive"))
      (node (ref "U4") (pin "36") (pinfunction "PB15_36") (pintype "bidirectional"))
    )
    (net (code "30") (name "G6P5") (class "Default")
      (node (ref "D42") (pin "A") (pinfunction "A_A") (pintype "passive"))
      (node (ref "D71") (pin "A") (pinfunction "A_A") (pintype "passive"))
      (node (ref "D75") (pin "A") (pinfunction "A_A") (pintype "passive"))
      (node (ref "D84") (pin "A") (pinfunction "A_A") (pintype "passive"))
      (node (ref "R37") (pin "2") (pinfunction "2_2") (pintype "passive"))
      (node (ref "U4") (pin "37") (pinfunction "PC6_37") (pintype "bidirectional"))
    )
    (net (code "31") (name "G6P6") (class "Default")
      (node (ref "D43") (pin "A") (pinfunction "A_A") (pintype "passive"))
      (node (ref "D76") (pin "A") (pinfunction "A_A") (pintype "passive"))
      (node (ref "D77") (pin "A") (pinfunction "A_A") (pintype "passive"))
      (node (ref "D85") (pin "A") (pinfunction "A_A") (pintype "passive"))
      (node (ref "U4") (pin "34") (pinfunction "PB13_34") (pintype "bidirectional"))
    )
    (net (code "32") (name "GND") (class "Default")
      (node (ref "C1") (pin "2") (pinfunction "2_2") (pintype "passive"))
      (node (ref "C10") (pin "1") (pinfunction "1_1") (pintype "passive"))
      (node (ref "C11") (pin "2") (pinfunction "2_2") (pintype "passive"))
      (node (ref "C12") (pin "2") (pinfunction "2_2") (pintype "passive"))
      (node (ref "C13") (pin "2") (pinfunction "2_2") (pintype "passive"))
      (node (ref "C14") (pin "-") (pinfunction "-_-") (pintype "passive"))
      (node (ref "C15") (pin "2") (pinfunction "2_2") (pintype "passive"))
      (node (ref "C16") (pin "2") (pinfunction "2_2") (pintype "passive"))
      (node (ref "C2") (pin "2") (pinfunction "2_2") (pintype "passive"))
      (node (ref "C3") (pin "2") (pinfunction "2_2") (pintype "passive"))
      (node (ref "C4") (pin "2") (pinfunction "2_2") (pintype "passive"))
      (node (ref "C7") (pin "1") (pinfunction "1_1") (pintype "passive"))
      (node (ref "C8") (pin "2") (pinfunction "2_2") (pintype "passive"))
      (node (ref "C9") (pin "2") (pinfunction "2_2") (pintype "passive"))
      (node (ref "J1") (pin "GND1") (pinfunction "GND_GND1") (pintype "bidirectional"))
      (node (ref "J1") (pin "GND2") (pinfunction "GND_GND2") (pintype "bidirectional"))
      (node (ref "J2") (pin "1") (pinfunction "2_1") (pintype "passive"))
      (node (ref "JP1") (pin "7") (pinfunction "7_7") (pintype "passive"))
      (node (ref "R1") (pin "1") (pinfunction "1_1") (pintype "passive"))
      (node (ref "R10") (pin "2") (pinfunction "2_2") (pintype "passive"))
      (node (ref "R2") (pin "1") (pinfunction "1_1") (pintype "passive"))
      (node (ref "R4") (pin "1") (pinfunction "1_1") (pintype "passive"))
      (node (ref "SW1") (pin "1") (pinfunction "P_1") (pintype "passive"))
      (node (ref "SW2") (pin "2") (pinfunction "VSS_2") (pintype "power_in"))
      (node (ref "U1") (pin "14") (pinfunction "TMR_14") (pintype "bidirectional"))
      (node (ref "U1") (pin "15") (pinfunction "SYSOFF_15") (pintype "bidirectional"))
      (node (ref "U1") (pin "17") (pinfunction "VSS_17") (pintype "bidirectional"))
      (node (ref "U1") (pin "4") (pinfunction "/CE_4") (pintype "bidirectional"))
      (node (ref "U1") (pin "5") (pinfunction "EN2_5") (pintype "bidirectional"))
      (node (ref "U1") (pin "8") (pinfunction "VSS_8") (pintype "bidirectional"))
      (node (ref "U2") (pin "1") (pinfunction "EN_1") (pintype "power_in"))
      (node (ref "U2") (pin "7") (pinfunction "VEE_7") (pintype "power_in"))
      (node (ref "U3") (pin "11") (pinfunction "PGND_11") (pintype "passive"))
      (node (ref "U3") (pin "3") (pinfunction "PGND_3") (pintype "passive"))
      (node (ref "U3") (pin "9") (pinfunction "GND_9") (pintype "passive"))
      (node (ref "U4") (pin "12") (pinfunction "VSSA_VREFM_12") (pintype "power_in"))
      (node (ref "U4") (pin "18") (pinfunction "VSS_18") (pintype "power_in"))
      (node (ref "U4") (pin "31") (pinfunction "VSS_31") (pintype "power_in"))
      (node (ref "U4") (pin "47") (pinfunction "VSS_47") (pintype "power_in"))
      (node (ref "U4") (pin "60") (pinfunction "BOOT0_60") (pintype "input"))
      (node (ref "U4") (pin "63") (pinfunction "VSS_63") (pintype "power_in"))
    )
    (net (code "33") (name "JTCK") (class "Default")
      (node (ref "JP1") (pin "5") (pinfunction "5_5") (pintype "passive"))
      (node (ref "U4") (pin "49") (pinfunction "JTCK_49") (pintype "input"))
    )
    (net (code "34") (name "JTDI") (class "Default")
      (node (ref "JP1") (pin "4") (pinfunction "4_4") (pintype "passive"))
      (node (ref "U4") (pin "50") (pinfunction "JTDI_50") (pintype "input"))
    )
    (net (code "35") (name "JTDO") (class "Default")
      (node (ref "JP1") (pin "3") (pinfunction "3_3") (pintype "passive"))
      (node (ref "U4") (pin "55") (pinfunction "JTDO_55") (pintype "output"))
    )
    (net (code "36") (name "JTMS") (class "Default")
      (node (ref "JP1") (pin "6") (pinfunction "6_6") (pintype "passive"))
      (node (ref "U4") (pin "46") (pinfunction "JTMS_46") (pintype "input"))
    )
    (net (code "37") (name "JTRST") (class "Default")
      (node (ref "JP1") (pin "2") (pinfunction "2_2") (pintype "passive"))
      (node (ref "U4") (pin "56") (pinfunction "JTRST_56") (pintype "input"))
    )
    (net (code "38") (name "Net-(C6-Pad2)") (class "Default")
      (node (ref "C6") (pin "2") (pinfunction "2_2") (pintype "passive"))
      (node (ref "R16") (pin "1") (pinfunction "1_1") (pintype "passive"))
    )
    (net (code "39") (name "Net-(D1-PadC)") (class "Default")
      (node (ref "D1") (pin "C") (pinfunction "C_C") (pintype "passive"))
      (node (ref "D2") (pin "C") (pinfunction "C_C") (pintype "passive"))
      (node (ref "D3") (pin "C") (pinfunction "C_C") (pintype "passive"))
      (node (ref "R20") (pin "1") (pinfunction "1_1") (pintype "passive"))
    )
    (net (code "40") (name "Net-(D4-PadC)") (class "Default")
      (node (ref "D4") (pin "C") (pinfunction "C_C") (pintype "passive"))
      (node (ref "D5") (pin "C") (pinfunction "C_C") (pintype "passive"))
      (node (ref "D6") (pin "C") (pinfunction "C_C") (pintype "passive"))
      (node (ref "R21") (pin "1") (pinfunction "1_1") (pintype "passive"))
    )
    (net (code "41") (name "Net-(D7-PadC)") (class "Default")
      (node (ref "D7") (pin "C") (pinfunction "C_C") (pintype "passive"))
      (node (ref "D8") (pin "C") (pinfunction "C_C") (pintype "passive"))
      (node (ref "R22") (pin "1") (pinfunction "1_1") (pintype "passive"))
    )
    (net (code "42") (name "Net-(D10-PadC)") (class "Default")
      (node (ref "D10") (pin "C") (pinfunction "C_C") (pintype "passive"))
      (node (ref "D11") (pin "C") (pinfunction "C_C") (pintype "passive"))
      (node (ref "D9") (pin "C") (pinfunction "C_C") (pintype "passive"))
      (node (ref "R6") (pin "1") (pinfunction "1_1") (pintype "passive"))
    )
    (net (code "43") (name "Net-(D12-PadC)") (class "Default")
      (node (ref "D12") (pin "C") (pinfunction "C_C") (pintype "passive"))
      (node (ref "D13") (pin "C") (pinfunction "C_C") (pintype "passive"))
      (node (ref "D14") (pin "C") (pinfunction "C_C") (pintype "passive"))
      (node (ref "R7") (pin "1") (pinfunction "1_1") (pintype "passive"))
    )
    (net (code "44") (name "Net-(D15-PadC)") (class "Default")
      (node (ref "D15") (pin "C") (pinfunction "C_C") (pintype "passive"))
      (node (ref "D16") (pin "C") (pinfunction "C_C") (pintype "passive"))
      (node (ref "D17") (pin "C") (pinfunction "C_C") (pintype "passive"))
      (node (ref "R8") (pin "1") (pinfunction "1_1") (pintype "passive"))
    )
    (net (code "45") (name "Net-(D18-PadC)") (class "Default")
      (node (ref "D18") (pin "C") (pinfunction "C_C") (pintype "passive"))
      (node (ref "R9") (pin "1") (pinfunction "1_1") (pintype "passive"))
    )
    (net (code "46") (name "Net-(D19-PadC)") (class "Default")
      (node (ref "D19") (pin "C") (pinfunction "C_C") (pintype "passive"))
      (node (ref "D24") (pin "C") (pinfunction "C_C") (pintype "passive"))
      (node (ref "R13") (pin "1") (pinfunction "1_1") (pintype "passive"))
    )
    (net (code "47") (name "Net-(D20-PadC)") (class "Default")
      (node (ref "D20") (pin "C") (pinfunction "C_C") (pintype "passive"))
      (node (ref "D21") (pin "C") (pinfunction "C_C") (pintype "passive"))
      (node (ref "R12") (pin "1") (pinfunction "1_1") (pintype "passive"))
    )
    (net (code "48") (name "Net-(D22-PadC)") (class "Default")
      (node (ref "D22") (pin "C") (pinfunction "C_C") (pintype "passive"))
      (node (ref "D23") (pin "C") (pinfunction "C_C") (pintype "passive"))
      (node (ref "R14") (pin "1") (pinfunction "1_1") (pintype "passive"))
    )
    (net (code "49") (name "Net-(D25-PadC)") (class "Default")
      (node (ref "D25") (pin "C") (pinfunction "C_C") (pintype "passive"))
      (node (ref "D26") (pin "C") (pinfunction "C_C") (pintype "passive"))
      (node (ref "D27") (pin "C") (pinfunction "C_C") (pintype "passive"))
      (node (ref "D28") (pin "C") (pinfunction "C_C") (pintype "passive"))
      (node (ref "R27") (pin "1") (pinfunction "1_1") (pintype "passive"))
    )
    (net (code "50") (name "Net-(D29-PadC)") (class "Default")
      (node (ref "D29") (pin "C") (pinfunction "C_C") (pintype "passive"))
      (node (ref "D30") (pin "C") (pinfunction "C_C") (pintype "passive"))
      (node (ref "D31") (pin "C") (pinfunction "C_C") (pintype "passive"))
      (node (ref "D32") (pin "C") (pinfunction "C_C") (pintype "passive"))
      (node (ref "R26") (pin "1") (pinfunction "1_1") (pintype "passive"))
    )
    (net (code "51") (name "Net-(D33-PadC)") (class "Default")
      (node (ref "D33") (pin "C") (pinfunction "C_C") (pintype "passive"))
      (node (ref "D36") (pin "C") (pinfunction "C_C") (pintype "passive"))
      (node (ref "DA1") (pin "C") (pinfunction "C_C") (pintype "passive"))
      (node (ref "DA2") (pin "C") (pinfunction "C_C") (pintype "passive"))
      (node (ref "R23") (pin "1") (pinfunction "1_1") (pintype "passive"))
    )
    (net (code "52") (name "Net-(D34-PadC)") (class "Default")
      (node (ref "D34") (pin "C") (pinfunction "C_C") (pintype "passive"))
      (node (ref "D37") (pin "C") (pinfunction "C_C") (pintype "passive"))
      (node (ref "DA4") (pin "C") (pinfunction "C_C") (pintype "passive"))
      (node (ref "DA6") (pin "C") (pinfunction "C_C") (pintype "passive"))
      (node (ref "R24") (pin "1") (pinfunction "1_1") (pintype "passive"))
    )
    (net (code "53") (name "Net-(D35-PadC)") (class "Default")
      (node (ref "D35") (pin "C") (pinfunction "C_C") (pintype "passive"))
      (node (ref "D38") (pin "C") (pinfunction "C_C") (pintype "passive"))
      (node (ref "DA3") (pin "C") (pinfunction "C_C") (pintype "passive"))
      (node (ref "DA5") (pin "C") (pinfunction "C_C") (pintype "passive"))
      (node (ref "R25") (pin "1") (pinfunction "1_1") (pintype "passive"))
    )
    (net (code "54") (name "Net-(D39-PadC)") (class "Default")
      (node (ref "D39") (pin "C") (pinfunction "C_C") (pintype "passive"))
      (node (ref "D40") (pin "C") (pinfunction "C_C") (pintype "passive"))
      (node (ref "D41") (pin "C") (pinfunction "C_C") (pintype "passive"))
      (node (ref "D42") (pin "C") (pinfunction "C_C") (pintype "passive"))
      (node (ref "D43") (pin "C") (pinfunction "C_C") (pintype "passive"))
      (node (ref "R35") (pin "1") (pinfunction "1_1") (pintype "passive"))
    )
    (net (code "55") (name "Net-(D44-PadC)") (class "Default")
      (node (ref "D44") (pin "C") (pinfunction "C_C") (pintype "passive"))
      (node (ref "D45") (pin "C") (pinfunction "C_C") (pintype "passive"))
      (node (ref "D46") (pin "C") (pinfunction "C_C") (pintype "passive"))
      (node (ref "D84") (pin "C") (pinfunction "C_C") (pintype "passive"))
      (node (ref "D85") (pin "C") (pinfunction "C_C") (pintype "passive"))
      (node (ref "R36") (pin "1") (pinfunction "1_1") (pintype "passive"))
    )
    (net (code "56") (name "Net-(D47-PadC)") (class "Default")
      (node (ref "D47") (pin "C") (pinfunction "C_C") (pintype "passive"))
      (node (ref "D48") (pin "C") (pinfunction "C_C") (pintype "passive"))
      (node (ref "D49") (pin "C") (pinfunction "C_C") (pintype "passive"))
      (node (ref "D80") (pin "C") (pinfunction "C_C") (pintype "passive"))
      (node (ref "R30") (pin "1") (pinfunction "1_1") (pintype "passive"))
    )
    (net (code "57") (name "Net-(D50-PadC)") (class "Default")
      (node (ref "D50") (pin "C") (pinfunction "C_C") (pintype "passive"))
      (node (ref "D51") (pin "C") (pinfunction "C_C") (pintype "passive"))
      (node (ref "D52") (pin "C") (pinfunction "C_C") (pintype "passive"))
      (node (ref "D81") (pin "C") (pinfunction "C_C") (pintype "passive"))
      (node (ref "R31") (pin "1") (pinfunction "1_1") (pintype "passive"))
    )
    (net (code "58") (name "Net-(D53-PadC)") (class "Default")
      (node (ref "D53") (pin "C") (pinfunction "C_C") (pintype "passive"))
      (node (ref "D54") (pin "C") (pinfunction "C_C") (pintype "passive"))
      (node (ref "D55") (pin "C") (pinfunction "C_C") (pintype "passive"))
      (node (ref "D82") (pin "C") (pinfunction "C_C") (pintype "passive"))
      (node (ref "R32") (pin "1") (pinfunction "1_1") (pintype "passive"))
    )
    (net (code "59") (name "Net-(D56-PadC)") (class "Default")
      (node (ref "D56") (pin "C") (pinfunction "C_C") (pintype "passive"))
      (node (ref "D57") (pin "C") (pinfunction "C_C") (pintype "passive"))
      (node (ref "D58") (pin "C") (pinfunction "C_C") (pintype "passive"))
      (node (ref "D79") (pin "C") (pinfunction "C_C") (pintype "passive"))
      (node (ref "D83") (pin "C") (pinfunction "C_C") (pintype "passive"))
      (node (ref "R28") (pin "1") (pinfunction "1_1") (pintype "passive"))
    )
    (net (code "60") (name "Net-(D59-PadC)") (class "Default")
      (node (ref "D59") (pin "C") (pinfunction "C_C") (pintype "passive"))
      (node (ref "D60") (pin "C") (pinfunction "C_C") (pintype "passive"))
      (node (ref "D61") (pin "C") (pinfunction "C_C") (pintype "passive"))
      (node (ref "D78") (pin "C") (pinfunction "C_C") (pintype "passive"))
      (node (ref "R29") (pin "1") (pinfunction "1_1") (pintype "passive"))
    )
    (net (code "61") (name "Net-(D68-PadC)") (class "Default")
      (node (ref "D68") (pin "C") (pinfunction "C_C") (pintype "passive"))
      (node (ref "D69") (pin "C") (pinfunction "C_C") (pintype "passive"))
      (node (ref "D70") (pin "C") (pinfunction "C_C") (pintype "passive"))
      (node (ref "D71") (pin "C") (pinfunction "C_C") (pintype "passive"))
      (node (ref "D76") (pin "C") (pinfunction "C_C") (pintype "passive"))
      (node (ref "R33") (pin "1") (pinfunction "1_1") (pintype "passive"))
    )
    (net (code "62") (name "Net-(D72-PadC)") (class "Default")
      (node (ref "D72") (pin "C") (pinfunction "C_C") (pintype "passive"))
      (node (ref "D73") (pin "C") (pinfunction "C_C") (pintype "passive"))
      (node (ref "D74") (pin "C") (pinfunction "C_C") (pintype "passive"))
      (node (ref "D75") (pin "C") (pinfunction "C_C") (pintype "passive"))
      (node (ref "D77") (pin "C") (pinfunction "C_C") (pintype "passive"))
      (node (ref "R34") (pin "1") (pinfunction "1_1") (pintype "passive"))
    )
    (net (code "63") (name "Net-(D86-PadC)") (class "Default")
      (node (ref "D86") (pin "C") (pinfunction "C_C") (pintype "passive"))
      (node (ref "D87") (pin "C") (pinfunction "C_C") (pintype "passive"))
      (node (ref "R37") (pin "1") (pinfunction "1_1") (pintype "passive"))
    )
    (net (code "64") (name "Net-(J1-CC-PadCC1)") (class "Default")
      (node (ref "J1") (pin "CC1") (pinfunction "CC_CC1") (pintype "passive"))
      (node (ref "J1") (pin "CC2") (pinfunction "CC_CC2") (pintype "passive"))
      (node (ref "R10") (pin "1") (pinfunction "1_1") (pintype "passive"))
    )
    (net (code "65") (name "Net-(J2-1)") (class "Default")
      (node (ref "J2") (pin "2") (pinfunction "1_2") (pintype "passive"))
      (node (ref "U1") (pin "2") (pinfunction "BAT_2") (pintype "bidirectional"))
      (node (ref "U1") (pin "3") (pinfunction "BAT_3") (pintype "bidirectional"))
    )
    (net (code "66") (name "Net-(SW1-S)") (class "Default")
      (node (ref "C10") (pin "2") (pinfunction "2_2") (pintype "passive"))
      (node (ref "R11") (pin "1") (pinfunction "1_1") (pintype "passive"))
      (node (ref "SW1") (pin "3") (pinfunction "S_3") (pintype "passive"))
      (node (ref "U4") (pin "7") (pinfunction "NRST_7") (pintype "input"))
    )
    (net (code "67") (name "Net-(U1-ILIM)") (class "Default")
      (node (ref "R2") (pin "2") (pinfunction "2_2") (pintype "passive"))
      (node (ref "U1") (pin "12") (pinfunction "ILIM_12") (pintype "bidirectional"))
    )
    (net (code "68") (name "Net-(U1-ISET)") (class "Default")
      (node (ref "R1") (pin "2") (pinfunction "2_2") (pintype "passive"))
      (node (ref "U1") (pin "16") (pinfunction "ISET_16") (pintype "bidirectional"))
    )
    (net (code "69") (name "Net-(U1-TS)") (class "Default")
      (node (ref "R3") (pin "1") (pinfunction "1_1") (pintype "passive"))
      (node (ref "R4") (pin "2") (pinfunction "2_2") (pintype "passive"))
      (node (ref "U1") (pin "1") (pinfunction "TS_1") (pintype "bidirectional"))
    )
    (net (code "70") (name "Net-(U2-BIAS)") (class "Default")
      (node (ref "C7") (pin "2") (pinfunction "2_2") (pintype "passive"))
      (node (ref "U2") (pin "2") (pinfunction "BIAS_2") (pintype "power_in"))
      (node (ref "U2") (pin "3") (pinfunction "IN+_3") (pintype "power_in"))
    )
    (net (code "71") (name "Net-(U2-IN-)") (class "Default")
      (node (ref "R16") (pin "2") (pinfunction "2_2") (pintype "passive"))
      (node (ref "R17") (pin "1") (pinfunction "1_1") (pintype "passive"))
      (node (ref "U2") (pin "4") (pinfunction "IN-_4") (pintype "power_in"))
    )
    (net (code "72") (name "Net-(U2-OUT+)") (class "Default")
      (node (ref "R17") (pin "2") (pinfunction "2_2") (pintype "passive"))
      (node (ref "SP1") (pin "2") (pinfunction "VSS_2") (pintype "power_in"))
      (node (ref "U2") (pin "5") (pinfunction "OUT+_5") (pintype "power_in"))
    )
    (net (code "73") (name "Net-(U2-OUT-)") (class "Default")
      (node (ref "SP1") (pin "1") (pinfunction "VSS_1") (pintype "power_in"))
      (node (ref "U2") (pin "8") (pinfunction "OUT-_8") (pintype "power_in"))
    )
    (net (code "74") (name "Net-(U3-EN)") (class "Default")
      (node (ref "C2") (pin "1") (pinfunction "1_1") (pintype "passive"))
      (node (ref "R5") (pin "1") (pinfunction "1_1") (pintype "passive"))
      (node (ref "U3") (pin "6") (pinfunction "EN_6") (pintype "passive"))
      (node (ref "U3") (pin "7") (pinfunction "PS/SYNC_7") (pintype "passive"))
      (node (ref "U3") (pin "8") (pinfunction "VINA_8") (pintype "passive"))
    )
    (net (code "75") (name "Net-(U3-L1)") (class "Default")
      (node (ref "L1") (pin "1") (pinfunction "1_1") (pintype "passive"))
      (node (ref "U3") (pin "4") (pinfunction "L1_4") (pintype "passive"))
    )
    (net (code "76") (name "Net-(U3-L2)") (class "Default")
      (node (ref "L1") (pin "2") (pinfunction "2_2") (pintype "passive"))
      (node (ref "U3") (pin "2") (pinfunction "L2_2") (pintype "passive"))
    )
    (net (code "77") (name "Net-(U4-PC13)") (class "Default")
      (node (ref "R15") (pin "1") (pinfunction "1_1") (pintype "passive"))
      (node (ref "SW2") (pin "1") (pinfunction "VSS_1") (pintype "power_in"))
      (node (ref "U4") (pin "2") (pinfunction "PC13_2") (pintype "bidirectional"))
    )
    (net (code "78") (name "TOUCH1") (class "Default")
      (node (ref "P1") (pin "P$1") (pinfunction "P$1_P$1") (pintype "bidirectional"))
      (node (ref "U4") (pin "14") (pinfunction "PA0_14") (pintype "bidirectional"))
    )
    (net (code "79") (name "TOUCH2") (class "Default")
      (node (ref "P2") (pin "P$1") (pinfunction "P$1_P$1") (pintype "bidirectional"))
      (node (ref "U4") (pin "16") (pinfunction "PA2_16") (pintype "bidirectional"))
    )
    (net (code "80") (name "TOUCH3") (class "Default")
      (node (ref "P3") (pin "P$1") (pinfunction "P$1_P$1") (pintype "bidirectional"))
      (node (ref "U4") (pin "15") (pinfunction "PA1_15") (pintype "bidirectional"))
    )
    (net (code "81") (name "TOUCH4") (class "Default")
      (node (ref "P4") (pin "P$1") (pinfunction "P$1_P$1") (pintype "bidirectional"))
      (node (ref "U4") (pin "58") (pinfunction "PB6_58") (pintype "bidirectional"))
    )
    (net (code "82") (name "TOUCH5") (class "Default")
      (node (ref "P5") (pin "P$1") (pinfunction "P$1_P$1") (pintype "bidirectional"))
      (node (ref "U4") (pin "28") (pinfunction "PB2_28") (pintype "bidirectional"))
    )
    (net (code "83") (name "TOUCH6") (class "Default")
      (node (ref "P6") (pin "P$1") (pinfunction "P$1_P$1") (pintype "bidirectional"))
      (node (ref "U4") (pin "27") (pinfunction "PB1_27") (pintype "bidirectional"))
    )
    (net (code "84") (name "TOUCH7") (class "Default")
      (node (ref "P7") (pin "P$1") (pinfunction "P$1_P$1") (pintype "bidirectional"))
      (node (ref "U4") (pin "26") (pinfunction "PB0_26") (pintype "bidirectional"))
    )
    (net (code "85") (name "VCC") (class "Default")
      (node (ref "C1") (pin "1") (pinfunction "1_1") (pintype "passive"))
      (node (ref "R5") (pin "2") (pinfunction "2_2") (pintype "passive"))
      (node (ref "U1") (pin "10") (pinfunction "OUT_10") (pintype "bidirectional"))
      (node (ref "U1") (pin "11") (pinfunction "OUT_11") (pintype "bidirectional"))
      (node (ref "U1") (pin "6") (pinfunction "EN1_6") (pintype "bidirectional"))
      (node (ref "U3") (pin "5") (pinfunction "VIN_5") (pintype "passive"))
    )
    (net (code "86") (name "unconnected-(U4-PA3-Pad17)") (class "Default")
      (node (ref "U4") (pin "17") (pinfunction "PA3_17") (pintype "bidirectional"))
    )
    (net (code "87") (name "unconnected-(U4-PA5-Pad21)") (class "Default")
      (node (ref "U4") (pin "21") (pinfunction "PA5_21") (pintype "bidirectional"))
    )
    (net (code "88") (name "unconnected-(U4-PA6-Pad22)") (class "Default")
      (node (ref "U4") (pin "22") (pinfunction "PA6_22") (pintype "bidirectional"))
    )
    (net (code "89") (name "unconnected-(U4-PB5-Pad57)") (class "Default")
      (node (ref "U4") (pin "57") (pinfunction "PB5_57") (pintype "bidirectional"))
    )
    (net (code "90") (name "unconnected-(U4-PB7-Pad59)") (class "Default")
      (node (ref "U4") (pin "59") (pinfunction "PB7_59") (pintype "bidirectional"))
    )
    (net (code "91") (name "unconnected-(U4-PC14_OSC32IN-Pad3)") (class "Default")
      (node (ref "U4") (pin "3") (pinfunction "PC14_OSC32IN_3") (pintype "bidirectional"))
    )
    (net (code "92") (name "unconnected-(U4-PC15_OSC32OU-Pad4)") (class "Default")
      (node (ref "U4") (pin "4") (pinfunction "PC15_OSC32OU_4") (pintype "bidirectional"))
    )
    (net (code "93") (name "{slash}CHG") (class "Default")
      (node (ref "R19") (pin "1") (pinfunction "1_1") (pintype "passive"))
      (node (ref "U1") (pin "9") (pinfunction "/CHG_9") (pintype "bidirectional"))
      (node (ref "U4") (pin "62") (pinfunction "PB9_62") (pintype "bidirectional"))
    )
    (net (code "94") (name "{slash}PGOOD") (class "Default")
      (node (ref "R18") (pin "1") (pinfunction "1_1") (pintype "passive"))
      (node (ref "U1") (pin "7") (pinfunction "/PGOOD_7") (pintype "bidirectional"))
      (node (ref "U4") (pin "61") (pinfunction "PB8_61") (pintype "bidirectional"))
    )
  )
)
